# Nerf_Driver.net
KiCad netlist of a schematic drawn in EAGLE
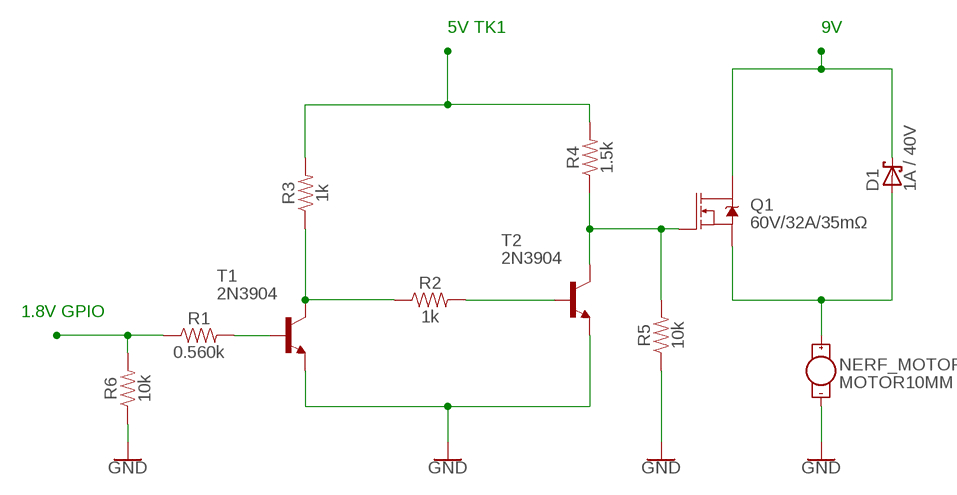
[diagram p0: schematic, sheet 1]

(export (version "E")
  (design (tool "Eeschema 10.0.6"))
  (components
    (comp (ref "D1")
      (value "1A / 40V")
      (footprint "eagle-import:CB429-17")
      (libsource (lib "eagle-import") (part "SCHOTTKY-DIODECB429-17"))
    )
    (comp (ref "NERF_MOTOR")
      (value "MOTOR10MM")
      (footprint "eagle-import:VIBE-MOTOR-10MM")
      (libsource (lib "eagle-import") (part "MOTOR10MM"))
    )
    (comp (ref "Q1")
      (value "60V/32A/35mΩ")
      (footprint "eagle-import:TO220V")
      (libsource (lib "eagle-import") (part "MOSFET-NCH-FQP30N06L"))
    )
    (comp (ref "R1")
      (value "0.560k")
      (footprint "eagle-import:AXIAL-0.3")
      (libsource (lib "eagle-import") (part "1KOHM-HORIZ-1/4W-5%"))
    )
    (comp (ref "R2")
      (value "1k")
      (footprint "eagle-import:AXIAL-0.3")
      (libsource (lib "eagle-import") (part "1KOHM-HORIZ-1/4W-5%"))
    )
    (comp (ref "R3")
      (value "1k")
      (footprint "eagle-import:AXIAL-0.3")
      (libsource (lib "eagle-import") (part "1KOHM-HORIZ-1/4W-5%"))
    )
    (comp (ref "R4")
      (value "1.5k")
      (footprint "eagle-import:AXIAL-0.3")
      (libsource (lib "eagle-import") (part "1KOHM-HORIZ-1/4W-5%"))
    )
    (comp (ref "R5")
      (value "10k")
      (footprint "eagle-import:AXIAL-0.3")
      (libsource (lib "eagle-import") (part "1KOHM-HORIZ-1/4W-5%"))
    )
    (comp (ref "R6")
      (value "10k")
      (footprint "eagle-import:AXIAL-0.3")
      (libsource (lib "eagle-import") (part "1KOHM-HORIZ-1/4W-5%"))
    )
    (comp (ref "T1")
      (value "2N3904")
      (footprint "eagle-import:TO92")
      (libsource (lib "eagle-import") (part "2N3904"))
    )
    (comp (ref "T2")
      (value "2N3904")
      (footprint "eagle-import:TO92")
      (libsource (lib "eagle-import") (part "2N3904"))
    )
  )
  (nets
    (net (code "1") (name "GND") (class "Default")
      (node (ref "NERF_MOTOR") (pin "-") (pinfunction "-_-") (pintype "bidirectional"))
      (node (ref "R5") (pin "P$1") (pinfunction "1_P$1") (pintype "passive"))
      (node (ref "R6") (pin "P$1") (pinfunction "1_P$1") (pintype "passive"))
      (node (ref "T1") (pin "3") (pinfunction "E_3") (pintype "passive"))
      (node (ref "T2") (pin "3") (pinfunction "E_3") (pintype "passive"))
    )
    (net (code "2") (name "Net-(Q1-D)") (class "Default")
      (node (ref "D1") (pin "C") (pinfunction "C_C") (pintype "passive"))
      (node (ref "Q1") (pin "2") (pinfunction "D_2") (pintype "bidirectional"))
    )
    (net (code "3") (name "Net-(Q1-G)") (class "Default")
      (node (ref "Q1") (pin "1") (pinfunction "G_1") (pintype "bidirectional"))
      (node (ref "R4") (pin "P$1") (pinfunction "1_P$1") (pintype "passive"))
      (node (ref "R5") (pin "P$2") (pinfunction "2_P$2") (pintype "passive"))
      (node (ref "T2") (pin "1") (pinfunction "C_1") (pintype "passive"))
    )
    (net (code "4") (name "Net-(Q1-S)") (class "Default")
      (node (ref "D1") (pin "A") (pinfunction "A_A") (pintype "passive"))
      (node (ref "NERF_MOTOR") (pin "+") (pinfunction "+_+") (pintype "bidirectional"))
      (node (ref "Q1") (pin "3") (pinfunction "S_3") (pintype "bidirectional"))
    )
    (net (code "5") (name "Net-(R1-1)") (class "Default")
      (node (ref "R1") (pin "P$1") (pinfunction "1_P$1") (pintype "passive"))
      (node (ref "R6") (pin "P$2") (pinfunction "2_P$2") (pintype "passive"))
    )
    (net (code "6") (name "Net-(R1-2)") (class "Default")
      (node (ref "R1") (pin "P$2") (pinfunction "2_P$2") (pintype "passive"))
      (node (ref "T1") (pin "2") (pinfunction "B_2") (pintype "passive"))
    )
    (net (code "7") (name "Net-(R2-1)") (class "Default")
      (node (ref "R2") (pin "P$1") (pinfunction "1_P$1") (pintype "passive"))
      (node (ref "R3") (pin "P$1") (pinfunction "1_P$1") (pintype "passive"))
      (node (ref "T1") (pin "1") (pinfunction "C_1") (pintype "passive"))
    )
    (net (code "8") (name "Net-(R2-2)") (class "Default")
      (node (ref "R2") (pin "P$2") (pinfunction "2_P$2") (pintype "passive"))
      (node (ref "T2") (pin "2") (pinfunction "B_2") (pintype "passive"))
    )
    (net (code "9") (name "Net-(R3-2)") (class "Default")
      (node (ref "R3") (pin "P$2") (pinfunction "2_P$2") (pintype "passive"))
      (node (ref "R4") (pin "P$2") (pinfunction "2_P$2") (pintype "passive"))
    )
  )
)
